# Power.net
KiCad netlist of a schematic drawn in Altium Designer
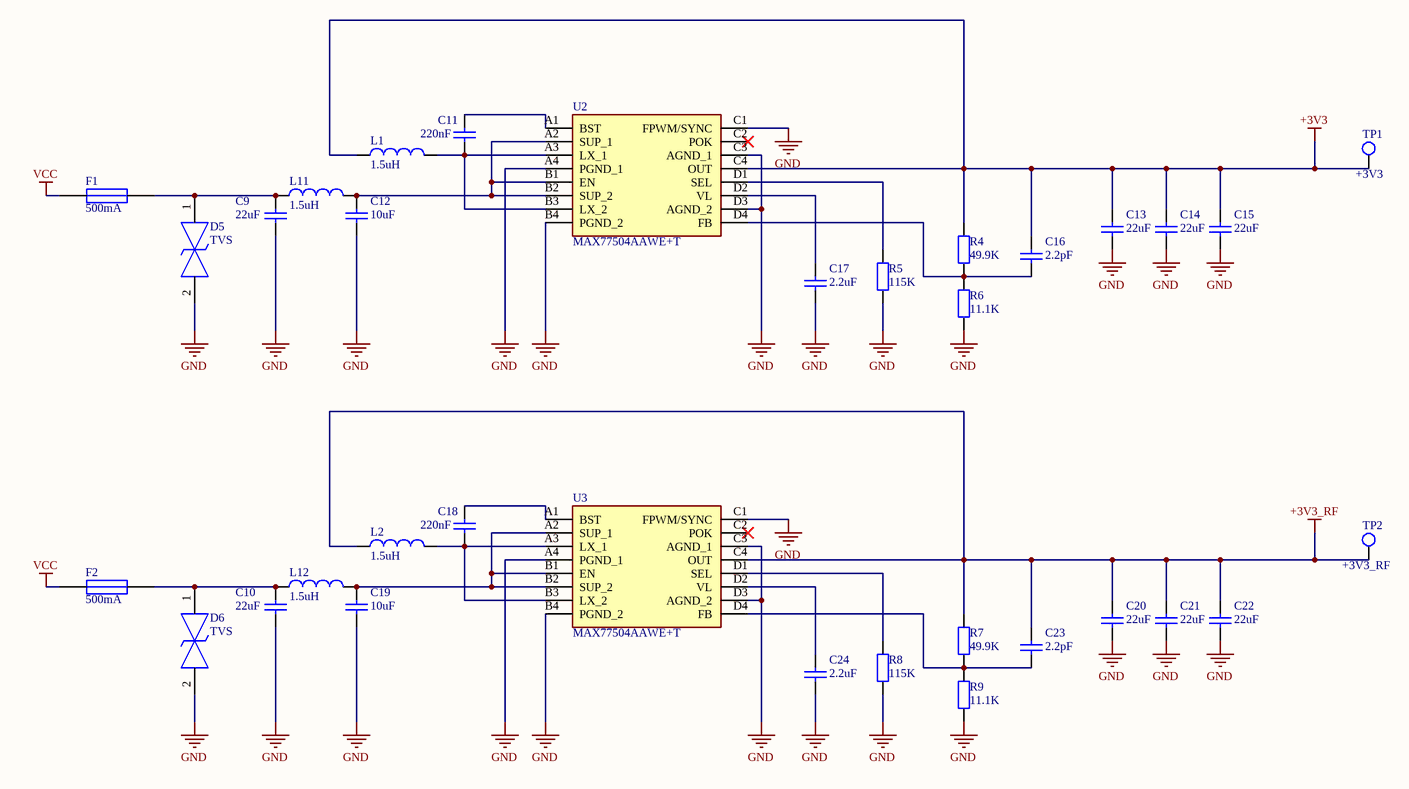
[diagram p0: Power.SchDoc]

(export (version "E")
  (design (tool "Eeschema 10.0.6"))
  (components
    (comp (ref "C9")
      (value "22uF")
      (footprint "0402")
      (description "Capacitor")
      (fields (field (name "Comment") "Cap") (field (name "PUBLISHER") "Altium Limited"))
      (libsource (lib "Miscellaneous Devices") (part "Cap"))
    )
    (comp (ref "C10")
      (value "22uF")
      (footprint "0402")
      (description "Capacitor")
      (fields (field (name "Comment") "Cap") (field (name "PUBLISHER") "Altium Limited"))
      (libsource (lib "Miscellaneous Devices") (part "Cap"))
    )
    (comp (ref "C11")
      (value "220nF")
      (footprint "0402")
      (description "Capacitor")
      (fields (field (name "Comment") "Cap") (field (name "PUBLISHER") "Altium Limited"))
      (libsource (lib "Miscellaneous Devices") (part "Cap"))
    )
    (comp (ref "C12")
      (value "10uF")
      (footprint "0402")
      (description "Capacitor")
      (fields (field (name "Comment") "Cap") (field (name "PUBLISHER") "Altium Limited"))
      (libsource (lib "Miscellaneous Devices") (part "Cap"))
    )
    (comp (ref "C13")
      (value "22uF")
      (footprint "0402")
      (description "Capacitor")
      (fields (field (name "Comment") "Cap") (field (name "PUBLISHER") "Altium Limited"))
      (libsource (lib "Miscellaneous Devices") (part "Cap"))
    )
    (comp (ref "C14")
      (value "22uF")
      (footprint "0402")
      (description "Capacitor")
      (fields (field (name "Comment") "Cap") (field (name "PUBLISHER") "Altium Limited"))
      (libsource (lib "Miscellaneous Devices") (part "Cap"))
    )
    (comp (ref "C15")
      (value "22uF")
      (footprint "0402")
      (description "Capacitor")
      (fields (field (name "Comment") "Cap") (field (name "PUBLISHER") "Altium Limited"))
      (libsource (lib "Miscellaneous Devices") (part "Cap"))
    )
    (comp (ref "C16")
      (value "2.2pF")
      (footprint "0402")
      (description "Capacitor")
      (fields (field (name "Comment") "Cap") (field (name "PUBLISHER") "Altium Limited"))
      (libsource (lib "Miscellaneous Devices") (part "Cap"))
    )
    (comp (ref "C17")
      (value "2.2uF")
      (footprint "0402")
      (description "Capacitor")
      (fields (field (name "Comment") "Cap") (field (name "PUBLISHER") "Altium Limited"))
      (libsource (lib "Miscellaneous Devices") (part "Cap"))
    )
    (comp (ref "C18")
      (value "220nF")
      (footprint "0402")
      (description "Capacitor")
      (fields (field (name "Comment") "Cap") (field (name "PUBLISHER") "Altium Limited"))
      (libsource (lib "Miscellaneous Devices") (part "Cap"))
    )
    (comp (ref "C19")
      (value "10uF")
      (footprint "0402")
      (description "Capacitor")
      (fields (field (name "Comment") "Cap") (field (name "PUBLISHER") "Altium Limited"))
      (libsource (lib "Miscellaneous Devices") (part "Cap"))
    )
    (comp (ref "C20")
      (value "22uF")
      (footprint "0402")
      (description "Capacitor")
      (fields (field (name "Comment") "Cap") (field (name "PUBLISHER") "Altium Limited"))
      (libsource (lib "Miscellaneous Devices") (part "Cap"))
    )
    (comp (ref "C21")
      (value "22uF")
      (footprint "0402")
      (description "Capacitor")
      (fields (field (name "Comment") "Cap") (field (name "PUBLISHER") "Altium Limited"))
      (libsource (lib "Miscellaneous Devices") (part "Cap"))
    )
    (comp (ref "C22")
      (value "22uF")
      (footprint "0402")
      (description "Capacitor")
      (fields (field (name "Comment") "Cap") (field (name "PUBLISHER") "Altium Limited"))
      (libsource (lib "Miscellaneous Devices") (part "Cap"))
    )
    (comp (ref "C23")
      (value "2.2pF")
      (footprint "0402")
      (description "Capacitor")
      (fields (field (name "Comment") "Cap") (field (name "PUBLISHER") "Altium Limited"))
      (libsource (lib "Miscellaneous Devices") (part "Cap"))
    )
    (comp (ref "C24")
      (value "2.2uF")
      (footprint "0402")
      (description "Capacitor")
      (fields (field (name "Comment") "Cap") (field (name "PUBLISHER") "Altium Limited"))
      (libsource (lib "Miscellaneous Devices") (part "Cap"))
    )
    (comp (ref "D5")
      (value "TVS")
      (footprint "TPD1E10B09DPYR")
      (fields
        (field (name "MOUSER PART NUMBER") "595-TPD1E10B09DPYR")
        (field (name "MANUFACTURER_PART_NUMBER") "TPD1E10B09DPYR")
      )
      (libsource (lib "Schematic_library") (part "TPD1E10B09DPYR"))
    )
    (comp (ref "D6")
      (value "TVS")
      (footprint "TPD1E10B09DPYR")
      (fields
        (field (name "MOUSER PART NUMBER") "595-TPD1E10B09DPYR")
        (field (name "MANUFACTURER_PART_NUMBER") "TPD1E10B09DPYR")
      )
      (libsource (lib "Schematic_library") (part "TPD1E10B09DPYR"))
    )
    (comp (ref "F1")
      (value "500mA")
      (footprint "SMD-1206-RES")
      (description "JB12S5000R\r\nSurface Mount Fuses JB12S SMD Fuse 63V 0.5A Slow 1206 3.2mm X 1.6mm")
      (fields
        (field (name "MOUSER PART NUMBER") "652-SF-1206S050-2")
        (field (name "MANUFACTURER_PART_NUMBER") "SF-1206S050-2")
      )
      (libsource (lib "Schematic_library") (part "Fuse"))
    )
    (comp (ref "F2")
      (value "500mA")
      (footprint "SMD-1206-RES")
      (description "JB12S5000R\r\nSurface Mount Fuses JB12S SMD Fuse 63V 0.5A Slow 1206 3.2mm X 1.6mm")
      (fields
        (field (name "MOUSER PART NUMBER") "652-SF-1206S050-2")
        (field (name "MANUFACTURER_PART_NUMBER") "SF-1206S050-2")
      )
      (libsource (lib "Schematic_library") (part "Fuse"))
    )
    (comp (ref "L1")
      (value "1.5uH")
      (footprint "0402-A")
      (description "Inductor")
      (fields (field (name "PUBLISHER") "Altium Limited"))
      (libsource (lib "Miscellaneous Devices") (part "Inductor"))
    )
    (comp (ref "L2")
      (value "1.5uH")
      (footprint "0402-A")
      (description "Inductor")
      (fields (field (name "PUBLISHER") "Altium Limited"))
      (libsource (lib "Miscellaneous Devices") (part "Inductor"))
    )
    (comp (ref "L11")
      (value "1.5uH")
      (footprint "0402-A")
      (description "Inductor")
      (fields (field (name "PUBLISHER") "Altium Limited"))
      (libsource (lib "Miscellaneous Devices") (part "Inductor"))
    )
    (comp (ref "L12")
      (value "1.5uH")
      (footprint "0402-A")
      (description "Inductor")
      (fields (field (name "PUBLISHER") "Altium Limited"))
      (libsource (lib "Miscellaneous Devices") (part "Inductor"))
    )
    (comp (ref "R4")
      (value "49.9K")
      (footprint "SMD-0402-RES")
      (description "Resistor")
      (fields (field (name "PUBLISHER") "Altium Limited"))
      (libsource (lib "Miscellaneous Devices") (part "Res2"))
    )
    (comp (ref "R5")
      (value "115K")
      (footprint "SMD-0402-RES")
      (description "Resistor")
      (fields (field (name "PUBLISHER") "Altium Limited"))
      (libsource (lib "Miscellaneous Devices") (part "Res2"))
    )
    (comp (ref "R6")
      (value "11.1K")
      (footprint "SMD-0402-RES")
      (description "Resistor")
      (fields (field (name "PUBLISHER") "Altium Limited"))
      (libsource (lib "Miscellaneous Devices") (part "Res2"))
    )
    (comp (ref "R7")
      (value "49.9K")
      (footprint "SMD-0402-RES")
      (description "Resistor")
      (fields (field (name "PUBLISHER") "Altium Limited"))
      (libsource (lib "Miscellaneous Devices") (part "Res2"))
    )
    (comp (ref "R8")
      (value "115K")
      (footprint "SMD-0402-RES")
      (description "Resistor")
      (fields (field (name "PUBLISHER") "Altium Limited"))
      (libsource (lib "Miscellaneous Devices") (part "Res2"))
    )
    (comp (ref "R9")
      (value "11.1K")
      (footprint "SMD-0402-RES")
      (description "Resistor")
      (fields (field (name "PUBLISHER") "Altium Limited"))
      (libsource (lib "Miscellaneous Devices") (part "Res2"))
    )
    (comp (ref "TP1")
      (value "+3V3")
      (footprint "testpoint 1 mm")
      (libsource (lib "Schematic_library") (part "testpoint"))
    )
    (comp (ref "TP2")
      (value "+3V3_RF")
      (footprint "testpoint 1 mm")
      (libsource (lib "Schematic_library") (part "testpoint"))
    )
    (comp (ref "U2")
      (value "MAX77504AAWE+T")
      (footprint "MAX77504AAWE+T")
      (description "Switching Voltage Regulators High-Efficiency Buck")
      (fields (field (name "MOUSER PART NUMBER") "700-MAX77504AAWE+T"))
      (libsource (lib "Schematic_library") (part "MAX77504AAWE+T"))
    )
    (comp (ref "U3")
      (value "MAX77504AAWE+T")
      (footprint "MAX77504AAWE+T")
      (description "Switching Voltage Regulators High-Efficiency Buck")
      (fields (field (name "MOUSER PART NUMBER") "700-MAX77504AAWE+T"))
      (libsource (lib "Schematic_library") (part "MAX77504AAWE+T"))
    )
  )
  (nets
    (net (code "1") (name "+3V3") (class "Default")
      (node (ref "C13") (pin "2") (pinfunction "2_2") (pintype "passive"))
      (node (ref "C14") (pin "2") (pinfunction "2_2") (pintype "passive"))
      (node (ref "C15") (pin "2") (pinfunction "2_2") (pintype "passive"))
      (node (ref "C16") (pin "2") (pinfunction "2_2") (pintype "passive"))
      (node (ref "L1") (pin "1") (pinfunction "1_1") (pintype "passive"))
      (node (ref "R4") (pin "2") (pinfunction "2_2") (pintype "passive"))
      (node (ref "TP1") (pin "1") (pinfunction "1_1") (pintype "passive"))
      (node (ref "U2") (pin "C4") (pinfunction "OUT_C4") (pintype "passive"))
    )
    (net (code "2") (name "+3V3_RF") (class "Default")
      (node (ref "C20") (pin "2") (pinfunction "2_2") (pintype "passive"))
      (node (ref "C21") (pin "2") (pinfunction "2_2") (pintype "passive"))
      (node (ref "C22") (pin "2") (pinfunction "2_2") (pintype "passive"))
      (node (ref "C23") (pin "2") (pinfunction "2_2") (pintype "passive"))
      (node (ref "L2") (pin "1") (pinfunction "1_1") (pintype "passive"))
      (node (ref "R7") (pin "2") (pinfunction "2_2") (pintype "passive"))
      (node (ref "TP2") (pin "1") (pinfunction "1_1") (pintype "passive"))
      (node (ref "U3") (pin "C4") (pinfunction "OUT_C4") (pintype "passive"))
    )
    (net (code "3") (name "GND") (class "Default")
      (node (ref "C10") (pin "1") (pinfunction "1_1") (pintype "passive"))
      (node (ref "C12") (pin "1") (pinfunction "1_1") (pintype "passive"))
      (node (ref "C13") (pin "1") (pinfunction "1_1") (pintype "passive"))
      (node (ref "C14") (pin "1") (pinfunction "1_1") (pintype "passive"))
      (node (ref "C15") (pin "1") (pinfunction "1_1") (pintype "passive"))
      (node (ref "C17") (pin "1") (pinfunction "1_1") (pintype "passive"))
      (node (ref "C19") (pin "1") (pinfunction "1_1") (pintype "passive"))
      (node (ref "C20") (pin "1") (pinfunction "1_1") (pintype "passive"))
      (node (ref "C21") (pin "1") (pinfunction "1_1") (pintype "passive"))
      (node (ref "C22") (pin "1") (pinfunction "1_1") (pintype "passive"))
      (node (ref "C24") (pin "1") (pinfunction "1_1") (pintype "passive"))
      (node (ref "C9") (pin "1") (pinfunction "1_1") (pintype "passive"))
      (node (ref "D5") (pin "2") (pinfunction "2_2") (pintype "passive"))
      (node (ref "D6") (pin "2") (pinfunction "2_2") (pintype "passive"))
      (node (ref "R5") (pin "1") (pinfunction "1_1") (pintype "passive"))
      (node (ref "R6") (pin "1") (pinfunction "1_1") (pintype "passive"))
      (node (ref "R8") (pin "1") (pinfunction "1_1") (pintype "passive"))
      (node (ref "R9") (pin "1") (pinfunction "1_1") (pintype "passive"))
      (node (ref "U2") (pin "A4") (pinfunction "PGND_1_A4") (pintype "passive"))
      (node (ref "U2") (pin "B4") (pinfunction "PGND_2_B4") (pintype "passive"))
      (node (ref "U2") (pin "C1") (pinfunction "FPWM/SYNC_C1") (pintype "passive"))
      (node (ref "U2") (pin "C3") (pinfunction "AGND_1_C3") (pintype "passive"))
      (node (ref "U2") (pin "D3") (pinfunction "AGND_2_D3") (pintype "passive"))
      (node (ref "U3") (pin "A4") (pinfunction "PGND_1_A4") (pintype "passive"))
      (node (ref "U3") (pin "B4") (pinfunction "PGND_2_B4") (pintype "passive"))
      (node (ref "U3") (pin "C1") (pinfunction "FPWM/SYNC_C1") (pintype "passive"))
      (node (ref "U3") (pin "C3") (pinfunction "AGND_1_C3") (pintype "passive"))
      (node (ref "U3") (pin "D3") (pinfunction "AGND_2_D3") (pintype "passive"))
    )
    (net (code "4") (name "Net-(C9-Pad2)") (class "Default")
      (node (ref "C9") (pin "2") (pinfunction "2_2") (pintype "passive"))
      (node (ref "D5") (pin "1") (pinfunction "1_1") (pintype "passive"))
      (node (ref "F1") (pin "2") (pinfunction "2_2") (pintype "passive"))
      (node (ref "L11") (pin "1") (pinfunction "1_1") (pintype "passive"))
    )
    (net (code "5") (name "Net-(C10-Pad2)") (class "Default")
      (node (ref "C10") (pin "2") (pinfunction "2_2") (pintype "passive"))
      (node (ref "D6") (pin "1") (pinfunction "1_1") (pintype "passive"))
      (node (ref "F2") (pin "2") (pinfunction "2_2") (pintype "passive"))
      (node (ref "L12") (pin "1") (pinfunction "1_1") (pintype "passive"))
    )
    (net (code "6") (name "Net-(U2-BST)") (class "Default")
      (node (ref "C11") (pin "2") (pinfunction "2_2") (pintype "passive"))
      (node (ref "U2") (pin "A1") (pinfunction "BST_A1") (pintype "passive"))
    )
    (net (code "7") (name "Net-(U2-EN)") (class "Default")
      (node (ref "C12") (pin "2") (pinfunction "2_2") (pintype "passive"))
      (node (ref "L11") (pin "2") (pinfunction "2_2") (pintype "passive"))
      (node (ref "U2") (pin "A2") (pinfunction "SUP_1_A2") (pintype "passive"))
      (node (ref "U2") (pin "B1") (pinfunction "EN_B1") (pintype "passive"))
      (node (ref "U2") (pin "B2") (pinfunction "SUP_2_B2") (pintype "passive"))
    )
    (net (code "8") (name "Net-(U2-FB)") (class "Default")
      (node (ref "C16") (pin "1") (pinfunction "1_1") (pintype "passive"))
      (node (ref "R4") (pin "1") (pinfunction "1_1") (pintype "passive"))
      (node (ref "R6") (pin "2") (pinfunction "2_2") (pintype "passive"))
      (node (ref "U2") (pin "D4") (pinfunction "FB_D4") (pintype "passive"))
    )
    (net (code "9") (name "Net-(U2-LX_1)") (class "Default")
      (node (ref "C11") (pin "1") (pinfunction "1_1") (pintype "passive"))
      (node (ref "L1") (pin "2") (pinfunction "2_2") (pintype "passive"))
      (node (ref "U2") (pin "A3") (pinfunction "LX_1_A3") (pintype "passive"))
      (node (ref "U2") (pin "B3") (pinfunction "LX_2_B3") (pintype "passive"))
    )
    (net (code "10") (name "Net-(U2-SEL)") (class "Default")
      (node (ref "R5") (pin "2") (pinfunction "2_2") (pintype "passive"))
      (node (ref "U2") (pin "D1") (pinfunction "SEL_D1") (pintype "passive"))
    )
    (net (code "11") (name "Net-(U2-VL)") (class "Default")
      (node (ref "C17") (pin "2") (pinfunction "2_2") (pintype "passive"))
      (node (ref "U2") (pin "D2") (pinfunction "VL_D2") (pintype "passive"))
    )
    (net (code "12") (name "Net-(U3-BST)") (class "Default")
      (node (ref "C18") (pin "2") (pinfunction "2_2") (pintype "passive"))
      (node (ref "U3") (pin "A1") (pinfunction "BST_A1") (pintype "passive"))
    )
    (net (code "13") (name "Net-(U3-EN)") (class "Default")
      (node (ref "C19") (pin "2") (pinfunction "2_2") (pintype "passive"))
      (node (ref "L12") (pin "2") (pinfunction "2_2") (pintype "passive"))
      (node (ref "U3") (pin "A2") (pinfunction "SUP_1_A2") (pintype "passive"))
      (node (ref "U3") (pin "B1") (pinfunction "EN_B1") (pintype "passive"))
      (node (ref "U3") (pin "B2") (pinfunction "SUP_2_B2") (pintype "passive"))
    )
    (net (code "14") (name "Net-(U3-FB)") (class "Default")
      (node (ref "C23") (pin "1") (pinfunction "1_1") (pintype "passive"))
      (node (ref "R7") (pin "1") (pinfunction "1_1") (pintype "passive"))
      (node (ref "R9") (pin "2") (pinfunction "2_2") (pintype "passive"))
      (node (ref "U3") (pin "D4") (pinfunction "FB_D4") (pintype "passive"))
    )
    (net (code "15") (name "Net-(U3-LX_1)") (class "Default")
      (node (ref "C18") (pin "1") (pinfunction "1_1") (pintype "passive"))
      (node (ref "L2") (pin "2") (pinfunction "2_2") (pintype "passive"))
      (node (ref "U3") (pin "A3") (pinfunction "LX_1_A3") (pintype "passive"))
      (node (ref "U3") (pin "B3") (pinfunction "LX_2_B3") (pintype "passive"))
    )
    (net (code "16") (name "Net-(U3-SEL)") (class "Default")
      (node (ref "R8") (pin "2") (pinfunction "2_2") (pintype "passive"))
      (node (ref "U3") (pin "D1") (pinfunction "SEL_D1") (pintype "passive"))
    )
    (net (code "17") (name "Net-(U3-VL)") (class "Default")
      (node (ref "C24") (pin "2") (pinfunction "2_2") (pintype "passive"))
      (node (ref "U3") (pin "D2") (pinfunction "VL_D2") (pintype "passive"))
    )
    (net (code "18") (name "VCC") (class "Default")
      (node (ref "F1") (pin "1") (pinfunction "1_1") (pintype "passive"))
      (node (ref "F2") (pin "1") (pinfunction "1_1") (pintype "passive"))
    )
    (net (code "19") (name "unconnected-(U2-POK-PadC2)") (class "Default")
      (node (ref "U2") (pin "C2") (pinfunction "POK_C2") (pintype "passive+no_connect"))
    )
    (net (code "20") (name "unconnected-(U3-POK-PadC2)") (class "Default")
      (node (ref "U3") (pin "C2") (pinfunction "POK_C2") (pintype "passive+no_connect"))
    )
  )
)
